# Design.net
KiCad netlist of a schematic drawn in EAGLE
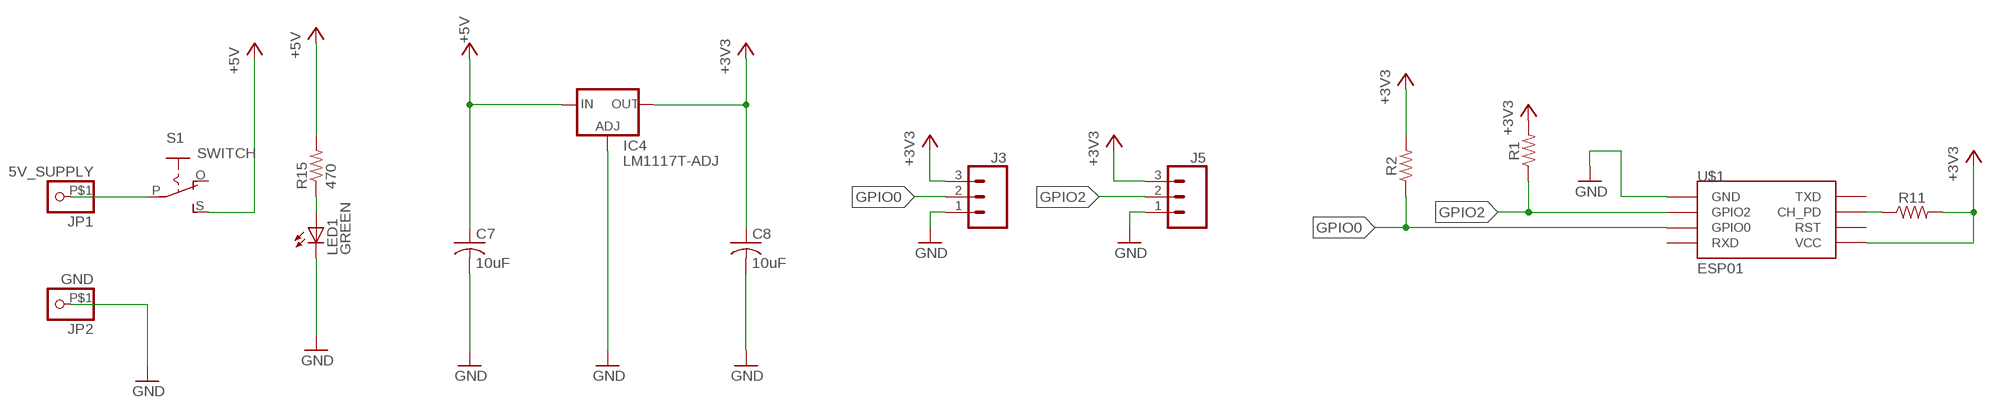
[diagram p0: schematic, sheet 1]

(export (version "E")
  (design (tool "Eeschema 10.0.6"))
  (components
    (comp (ref "C7")
      (value "10uF")
      (footprint "eagle-import:C025-025X050")
      (libsource (lib "eagle-import") (part "C-US025-025X050"))
    )
    (comp (ref "C8")
      (value "10uF")
      (footprint "eagle-import:C025-025X050")
      (libsource (lib "eagle-import") (part "C-US025-025X050"))
    )
    (comp (ref "IC4")
      (value "LM1117T-ADJ")
      (footprint "eagle-import:TO220")
      (libsource (lib "eagle-import") (part "LM1117T-ADJ"))
    )
    (comp (ref "J3")
      (value "1x3 RA Female .1\"")
      (footprint "eagle-import:1X03")
      (libsource (lib "eagle-import") (part "CONN_03"))
    )
    (comp (ref "J5")
      (value "1x3 RA Female .1\"")
      (footprint "eagle-import:1X03")
      (libsource (lib "eagle-import") (part "CONN_03"))
    )
    (comp (ref "JP1")
      (value "5V_SUPPLY")
      (footprint "eagle-import:1X1-BIGPOGO")
      (libsource (lib "eagle-import") (part "PINHD-1X1-BIGPOGO"))
    )
    (comp (ref "JP2")
      (value "GND")
      (footprint "eagle-import:1X1-BIGPOGO")
      (libsource (lib "eagle-import") (part "PINHD-1X1-BIGPOGO"))
    )
    (comp (ref "LED1")
      (value "GREEN")
      (footprint "eagle-import:LED5MM")
      (libsource (lib "eagle-import") (part "LED5MM"))
    )
    (comp (ref "R1")
      (value "10k")
      (footprint "eagle-import:0207_12")
      (libsource (lib "eagle-import") (part "R-US_0207/12"))
    )
    (comp (ref "R2")
      (value "10k")
      (footprint "eagle-import:0207_12")
      (libsource (lib "eagle-import") (part "R-US_0207/12"))
    )
    (comp (ref "R11")
      (value "10k")
      (footprint "eagle-import:0207_12")
      (libsource (lib "eagle-import") (part "R-US_0207/12"))
    )
    (comp (ref "R15")
      (value "470")
      (footprint "eagle-import:0207_12")
      (libsource (lib "eagle-import") (part "R-US_0207/12"))
    )
    (comp (ref "S1")
      (value "SWITCH")
      (footprint "eagle-import:EG1218")
      (libsource (lib "eagle-import") (part "EG1218S"))
    )
    (comp (ref "U$1")
      (value "ESP01")
      (footprint "eagle-import:ESP01")
      (libsource (lib "eagle-import") (part "ESP01"))
    )
  )
  (nets
    (net (code "1") (name "+3V3") (class "Default")
      (node (ref "C8") (pin "1") (pinfunction "1_1") (pintype "passive"))
      (node (ref "IC4") (pin "2") (pinfunction "OUT_2") (pintype "passive"))
      (node (ref "J3") (pin "3") (pinfunction "3_3") (pintype "passive"))
      (node (ref "J5") (pin "3") (pinfunction "3_3") (pintype "passive"))
      (node (ref "R1") (pin "2") (pinfunction "2_2") (pintype "passive"))
      (node (ref "R11") (pin "2") (pinfunction "2_2") (pintype "passive"))
      (node (ref "R2") (pin "2") (pinfunction "2_2") (pintype "passive"))
      (node (ref "U$1") (pin "VCC") (pinfunction "VCC_VCC") (pintype "bidirectional"))
    )
    (net (code "2") (name "+5V") (class "Default")
      (node (ref "C7") (pin "1") (pinfunction "1_1") (pintype "passive"))
      (node (ref "IC4") (pin "3") (pinfunction "IN_3") (pintype "input"))
      (node (ref "R15") (pin "2") (pinfunction "2_2") (pintype "passive"))
      (node (ref "S1") (pin "S") (pinfunction "S_S") (pintype "passive"))
    )
    (net (code "3") (name "GND") (class "Default")
      (node (ref "C7") (pin "2") (pinfunction "2_2") (pintype "passive"))
      (node (ref "C8") (pin "2") (pinfunction "2_2") (pintype "passive"))
      (node (ref "IC4") (pin "1") (pinfunction "ADJ_1") (pintype "input"))
      (node (ref "J3") (pin "1") (pinfunction "1_1") (pintype "passive"))
      (node (ref "J5") (pin "1") (pinfunction "1_1") (pintype "passive"))
      (node (ref "JP2") (pin "P$1") (pinfunction "1_P$1") (pintype "passive"))
      (node (ref "LED1") (pin "K") (pinfunction "C_K") (pintype "passive"))
      (node (ref "U$1") (pin "GND") (pinfunction "GND_GND") (pintype "bidirectional"))
    )
    (net (code "4") (name "GPIO0") (class "Default")
      (node (ref "J3") (pin "2") (pinfunction "2_2") (pintype "passive"))
      (node (ref "R2") (pin "1") (pinfunction "1_1") (pintype "passive"))
      (node (ref "U$1") (pin "GPIO0") (pinfunction "GPIO0_GPIO0") (pintype "bidirectional"))
    )
    (net (code "5") (name "GPIO2") (class "Default")
      (node (ref "J5") (pin "2") (pinfunction "2_2") (pintype "passive"))
      (node (ref "R1") (pin "1") (pinfunction "1_1") (pintype "passive"))
      (node (ref "U$1") (pin "GPIO2") (pinfunction "GPIO2_GPIO2") (pintype "bidirectional"))
    )
    (net (code "6") (name "Net-(JP1-1)") (class "Default")
      (node (ref "JP1") (pin "P$1") (pinfunction "1_P$1") (pintype "passive"))
      (node (ref "S1") (pin "P") (pinfunction "P_P") (pintype "passive"))
    )
    (net (code "7") (name "Net-(LED1-PadA)") (class "Default")
      (node (ref "LED1") (pin "A") (pinfunction "A_A") (pintype "passive"))
      (node (ref "R15") (pin "1") (pinfunction "1_1") (pintype "passive"))
    )
    (net (code "8") (name "Net-(R11-Pad1)") (class "Default")
      (node (ref "R11") (pin "1") (pinfunction "1_1") (pintype "passive"))
      (node (ref "U$1") (pin "CH_PD") (pinfunction "CH_PD_CH_PD") (pintype "bidirectional"))
    )
    (net (code "9") (name "unconnected-(S1-PadO)") (class "Default")
      (node (ref "S1") (pin "O") (pinfunction "O_O") (pintype "passive"))
    )
    (net (code "10") (name "unconnected-(U$1-PadRST)") (class "Default")
      (node (ref "U$1") (pin "RST") (pinfunction "RST_RST") (pintype "bidirectional"))
    )
    (net (code "11") (name "unconnected-(U$1-RXD-PadRX)") (class "Default")
      (node (ref "U$1") (pin "RX") (pinfunction "RXD_RX") (pintype "bidirectional"))
    )
    (net (code "12") (name "unconnected-(U$1-TXD-PadTX)") (class "Default")
      (node (ref "U$1") (pin "TX") (pinfunction "TXD_TX") (pintype "bidirectional"))
    )
  )
)
